# SwitchEthernet_-_Rev_A3.net
KiCad netlist of a schematic drawn in EAGLE
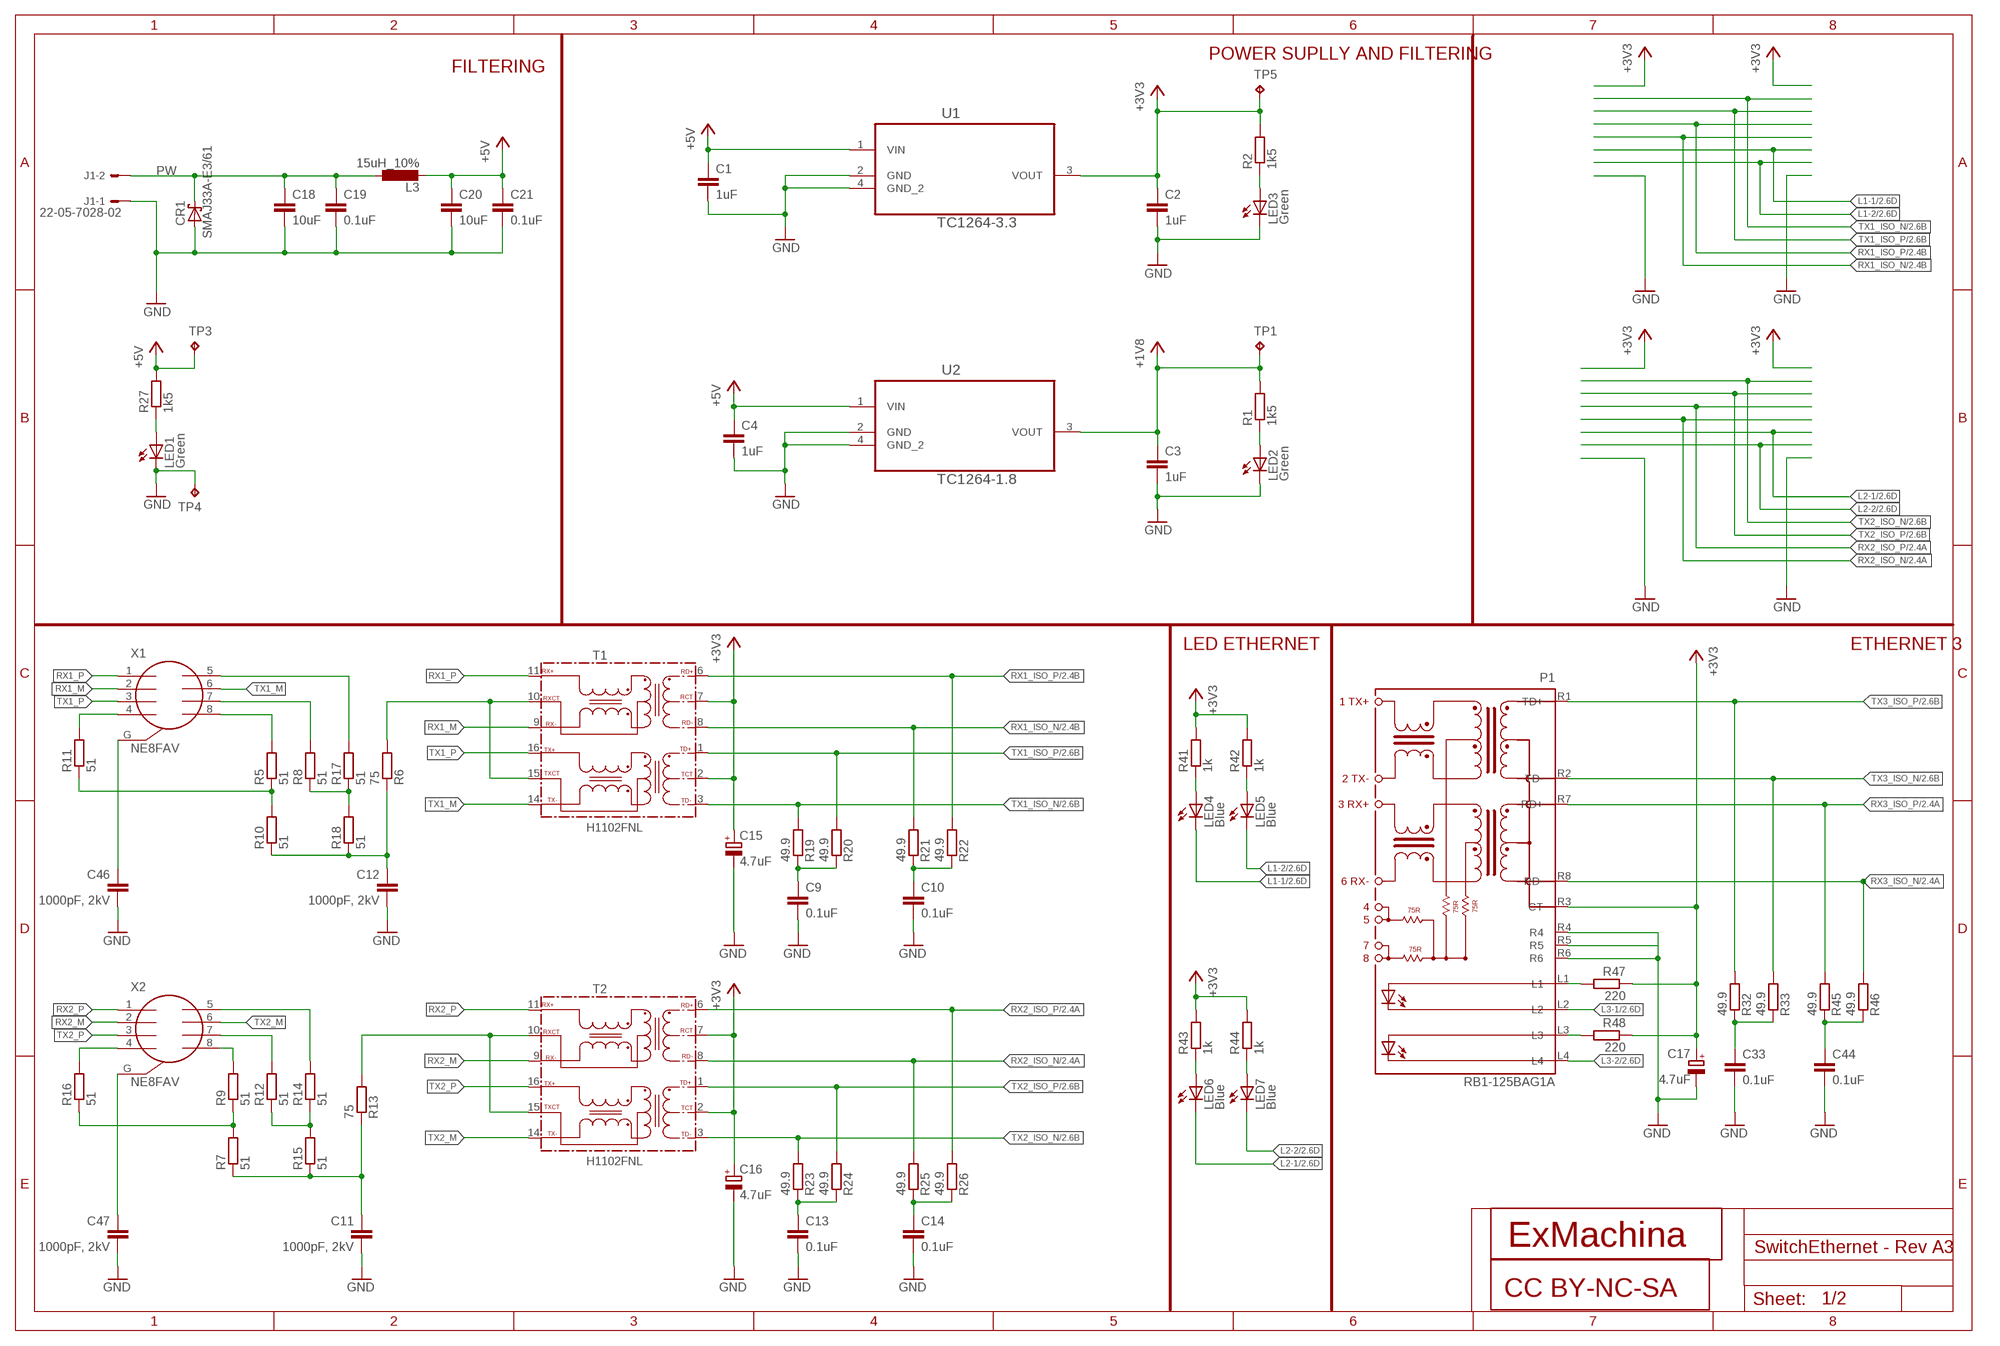
[diagram p0: schematic, sheet 1]
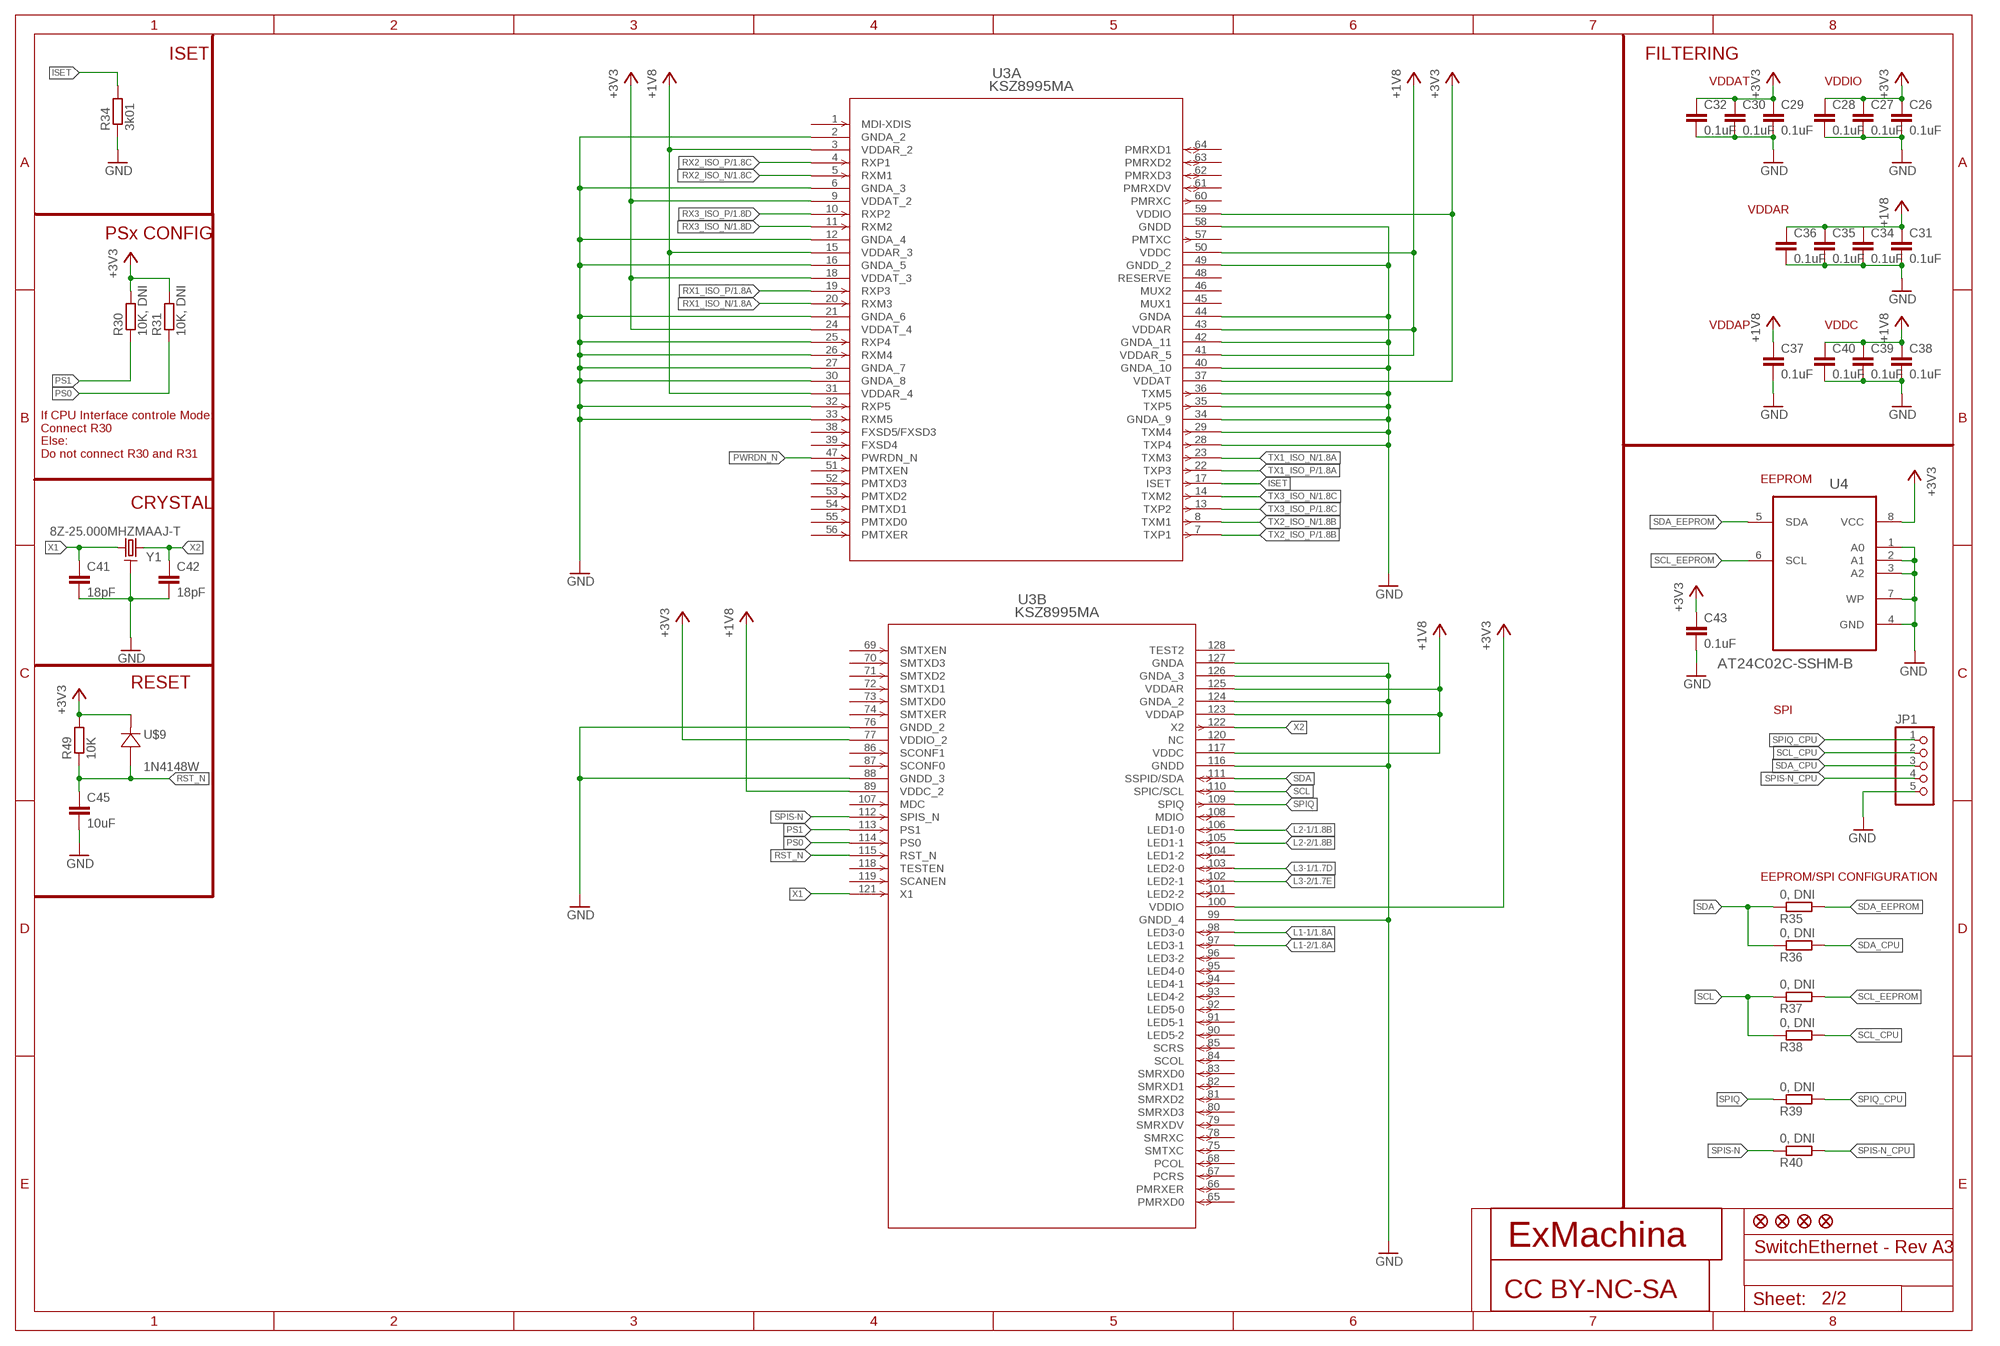
[diagram p1: schematic, sheet 2]

(export (version "E")
  (design (tool "Eeschema 10.0.6"))
  (components
    (comp (ref "C26")
      (value "0.1uF")
      (footprint "eagle-import:C0603")
      (fields (field (name "MF") "MULTICOMP") (field (name "MPN") "MC0603B104K250CT"))
      (libsource (lib "eagle-import") (part "C-EUC0603"))
    )
    (comp (ref "C27")
      (value "0.1uF")
      (footprint "eagle-import:C0603")
      (fields (field (name "MF") "MULTICOMP") (field (name "MPN") "MC0603B104K250CT"))
      (libsource (lib "eagle-import") (part "C-EUC0603"))
    )
    (comp (ref "C28")
      (value "0.1uF")
      (footprint "eagle-import:C0603")
      (fields (field (name "MF") "MULTICOMP") (field (name "MPN") "MC0603B104K250CT"))
      (libsource (lib "eagle-import") (part "C-EUC0603"))
    )
    (comp (ref "C29")
      (value "0.1uF")
      (footprint "eagle-import:C0603")
      (fields (field (name "MF") "MULTICOMP") (field (name "MPN") "MC0603B104K250CT"))
      (libsource (lib "eagle-import") (part "C-EUC0603"))
    )
    (comp (ref "C30")
      (value "0.1uF")
      (footprint "eagle-import:C0603")
      (fields (field (name "MF") "MULTICOMP") (field (name "MPN") "MC0603B104K250CT"))
      (libsource (lib "eagle-import") (part "C-EUC0603"))
    )
    (comp (ref "C31")
      (value "0.1uF")
      (footprint "eagle-import:C0603")
      (fields (field (name "MF") "MULTICOMP") (field (name "MPN") "MC0603B104K250CT"))
      (libsource (lib "eagle-import") (part "C-EUC0603"))
    )
    (comp (ref "C32")
      (value "0.1uF")
      (footprint "eagle-import:C0603")
      (fields (field (name "MF") "MULTICOMP") (field (name "MPN") "MC0603B104K250CT"))
      (libsource (lib "eagle-import") (part "C-EUC0603"))
    )
    (comp (ref "C34")
      (value "0.1uF")
      (footprint "eagle-import:C0603")
      (fields (field (name "MF") "MULTICOMP") (field (name "MPN") "MC0603B104K250CT"))
      (libsource (lib "eagle-import") (part "C-EUC0603"))
    )
    (comp (ref "C35")
      (value "0.1uF")
      (footprint "eagle-import:C0603")
      (fields (field (name "MF") "MULTICOMP") (field (name "MPN") "MC0603B104K250CT"))
      (libsource (lib "eagle-import") (part "C-EUC0603"))
    )
    (comp (ref "C36")
      (value "0.1uF")
      (footprint "eagle-import:C0603")
      (fields (field (name "MF") "MULTICOMP") (field (name "MPN") "MC0603B104K250CT"))
      (libsource (lib "eagle-import") (part "C-EUC0603"))
    )
    (comp (ref "C37")
      (value "0.1uF")
      (footprint "eagle-import:C0603")
      (fields (field (name "MF") "MULTICOMP") (field (name "MPN") "MC0603B104K250CT"))
      (libsource (lib "eagle-import") (part "C-EUC0603"))
    )
    (comp (ref "C38")
      (value "0.1uF")
      (footprint "eagle-import:C0603")
      (fields (field (name "MF") "MULTICOMP") (field (name "MPN") "MC0603B104K250CT"))
      (libsource (lib "eagle-import") (part "C-EUC0603"))
    )
    (comp (ref "C39")
      (value "0.1uF")
      (footprint "eagle-import:C0603")
      (fields (field (name "MF") "MULTICOMP") (field (name "MPN") "MC0603B104K250CT"))
      (libsource (lib "eagle-import") (part "C-EUC0603"))
    )
    (comp (ref "C40")
      (value "0.1uF")
      (footprint "eagle-import:C0603")
      (fields (field (name "MF") "MULTICOMP") (field (name "MPN") "MC0603B104K250CT"))
      (libsource (lib "eagle-import") (part "C-EUC0603"))
    )
    (comp (ref "C41")
      (value "18pF")
      (footprint "eagle-import:C0603")
      (fields (field (name "MF") "MULTICOMP") (field (name "MPN") "MC0603B183K160CT"))
      (libsource (lib "eagle-import") (part "C-EUC0603"))
    )
    (comp (ref "C42")
      (value "18pF")
      (footprint "eagle-import:C0603")
      (fields (field (name "MF") "MULTICOMP") (field (name "MPN") "MC0603B183K160CT"))
      (libsource (lib "eagle-import") (part "C-EUC0603"))
    )
    (comp (ref "C43")
      (value "0.1uF")
      (footprint "eagle-import:C0603")
      (fields (field (name "MF") "MULTICOMP") (field (name "MPN") "MC0603B104K250CT"))
      (libsource (lib "eagle-import") (part "C-EUC0603"))
    )
    (comp (ref "C45")
      (value "10uF")
      (footprint "eagle-import:C0603")
      (fields (field (name "MF") "MURATA") (field (name "MPN") "GRM32DR71C106KA01L"))
      (libsource (lib "eagle-import") (part "C-EUC0603"))
    )
    (comp (ref "JP1")
      (value "PINHD-1X5")
      (footprint "eagle-import:1X05")
      (libsource (lib "eagle-import") (part "PINHD-1X5"))
    )
    (comp (ref "JP7")
      (value "FIDUCIAL1X2")
      (footprint "eagle-import:FIDUCIAL-1X2")
      (libsource (lib "eagle-import") (part "FIDUCIAL1X2"))
    )
    (comp (ref "JP8")
      (value "FIDUCIAL1X2")
      (footprint "eagle-import:FIDUCIAL-1X2")
      (libsource (lib "eagle-import") (part "FIDUCIAL1X2"))
    )
    (comp (ref "JP9")
      (value "FIDUCIAL1X2")
      (footprint "eagle-import:FIDUCIAL-1X2")
      (libsource (lib "eagle-import") (part "FIDUCIAL1X2"))
    )
    (comp (ref "JP10")
      (value "FIDUCIAL1X2")
      (footprint "eagle-import:FIDUCIAL-1X2")
      (libsource (lib "eagle-import") (part "FIDUCIAL1X2"))
    )
    (comp (ref "R30")
      (value "10K, DNI")
      (footprint "eagle-import:R0603")
      (libsource (lib "eagle-import") (part "R-EU_R0603"))
    )
    (comp (ref "R31")
      (value "10K, DNI")
      (footprint "eagle-import:R0603")
      (libsource (lib "eagle-import") (part "R-EU_R0603"))
    )
    (comp (ref "R34")
      (value "3k01")
      (footprint "eagle-import:R0603")
      (fields (field (name "MF") "MULTICOMP") (field (name "MPN") "MCMR06X3001FTL"))
      (libsource (lib "eagle-import") (part "R-EU_R0603"))
    )
    (comp (ref "R35")
      (value "0, DNI")
      (footprint "eagle-import:R0603")
      (libsource (lib "eagle-import") (part "R-EU_R0603"))
    )
    (comp (ref "R36")
      (value "0, DNI")
      (footprint "eagle-import:R0603")
      (libsource (lib "eagle-import") (part "R-EU_R0603"))
    )
    (comp (ref "R37")
      (value "0, DNI")
      (footprint "eagle-import:R0603")
      (libsource (lib "eagle-import") (part "R-EU_R0603"))
    )
    (comp (ref "R38")
      (value "0, DNI")
      (footprint "eagle-import:R0603")
      (libsource (lib "eagle-import") (part "R-EU_R0603"))
    )
    (comp (ref "R39")
      (value "0, DNI")
      (footprint "eagle-import:R0603")
      (libsource (lib "eagle-import") (part "R-EU_R0603"))
    )
    (comp (ref "R40")
      (value "0, DNI")
      (footprint "eagle-import:R0603")
      (libsource (lib "eagle-import") (part "R-EU_R0603"))
    )
    (comp (ref "R49")
      (value "10K")
      (footprint "eagle-import:R0603")
      (fields (field (name "MF") "MULTICOMP") (field (name "MPN") "MCMR06X1002FTL"))
      (libsource (lib "eagle-import") (part "R-EU_R0603"))
    )
    (comp (ref "U$7")
      (value "CC-BY-NC-SA")
      (footprint "eagle-import:CC-BY-NC-SA")
      (libsource (lib "eagle-import") (part "CC-BY-NC-SA"))
    )
    (comp (ref "U$8")
      (value "EXMACHINA-LOGO-NAME")
      (footprint "eagle-import:EXM-LOGO-BASELINE")
      (libsource (lib "eagle-import") (part "EXMACHINA-LOGO-NAME"))
    )
    (comp (ref "U$9")
      (value "1N4148W")
      (footprint "eagle-import:SOD-123_MINI-SMA")
      (libsource (lib "eagle-import") (part "1N4148W"))
    )
    (comp (ref "U3")
      (value "KSZ8995MA")
      (footprint "eagle-import:PQFP-128_MQL")
      (fields
        (field (name "MANUFACTURER_PART_NUMBER") "ksz8995ma")
        (field (name "MF") "MICROCHIP")
        (field (name "MPN") "KSZ8995MA")
        (field (name "OC_FARNELL") "2509844")
        (field (name "OC_NEWARK") "70Y9044")
        (field (name "COPYRIGHT") "Copyright (C) 2015 Accelerated Designs. All rights reserved")
      )
      (libsource (lib "eagle-import") (part "KSZ8995MA"))
    )
    (comp (ref "U4")
      (value "AT24C02C-SSHM-B")
      (footprint "eagle-import:SOIC127P600X175-8N")
      (fields (field (name "MF") "ATMEL") (field (name "OC_FARNELL") "1971995"))
      (libsource (lib "eagle-import") (part "AT24C02C-SSHM-B"))
    )
    (comp (ref "Y1")
      (value "8Z-25.000MHZMAAJ-T")
      (footprint "eagle-import:SMD2.5X2")
      (fields (field (name "MF") "TXC") (field (name "MPN") "8Z-25.000MAAJ-T"))
      (libsource (lib "eagle-import") (part "8Z-25.000MHZMAAJ-T"))
    )
    (comp (ref "C1")
      (value "1uF")
      (footprint "eagle-import:C0603")
      (libsource (lib "eagle-import") (part "C-EUC0603"))
    )
    (comp (ref "C2")
      (value "1uF")
      (footprint "eagle-import:C0603")
      (libsource (lib "eagle-import") (part "C-EUC0603"))
    )
    (comp (ref "C3")
      (value "1uF")
      (footprint "eagle-import:C0603")
      (libsource (lib "eagle-import") (part "C-EUC0603"))
    )
    (comp (ref "C4")
      (value "1uF")
      (footprint "eagle-import:C0603")
      (libsource (lib "eagle-import") (part "C-EUC0603"))
    )
    (comp (ref "C9")
      (value "0.1uF")
      (footprint "eagle-import:C0603")
      (fields (field (name "MF") "MULTICOMP") (field (name "MPN") "MC0603B104K250CT"))
      (libsource (lib "eagle-import") (part "C-EUC0603"))
    )
    (comp (ref "C10")
      (value "0.1uF")
      (footprint "eagle-import:C0603")
      (fields (field (name "MF") "MULTICOMP") (field (name "MPN") "MC0603B104K250CT"))
      (libsource (lib "eagle-import") (part "C-EUC0603"))
    )
    (comp (ref "C11")
      (value "1000pF, 2kV")
      (footprint "eagle-import:C1206")
      (libsource (lib "eagle-import") (part "C-EUC1206"))
    )
    (comp (ref "C12")
      (value "1000pF, 2kV")
      (footprint "eagle-import:C1206")
      (libsource (lib "eagle-import") (part "C-EUC1206"))
    )
    (comp (ref "C13")
      (value "0.1uF")
      (footprint "eagle-import:C0603")
      (fields (field (name "MF") "MULTICOMP") (field (name "MPN") "MC0603B104K250CT"))
      (libsource (lib "eagle-import") (part "C-EUC0603"))
    )
    (comp (ref "C14")
      (value "0.1uF")
      (footprint "eagle-import:C0603")
      (fields (field (name "MF") "MULTICOMP") (field (name "MPN") "MC0603B104K250CT"))
      (libsource (lib "eagle-import") (part "C-EUC0603"))
    )
    (comp (ref "C15")
      (value "4.7uF")
      (footprint "eagle-import:CT3216")
      (libsource (lib "eagle-import") (part "CPOL-EUCT3216"))
    )
    (comp (ref "C16")
      (value "4.7uF")
      (footprint "eagle-import:CT3216")
      (libsource (lib "eagle-import") (part "CPOL-EUCT3216"))
    )
    (comp (ref "C17")
      (value "4.7uF")
      (footprint "eagle-import:CT3216")
      (libsource (lib "eagle-import") (part "CPOL-EUCT3216"))
    )
    (comp (ref "C18")
      (value "10uF")
      (footprint "eagle-import:C0603")
      (fields (field (name "MF") "MURATA") (field (name "MPN") "GRM32DR71C106KA01L"))
      (libsource (lib "eagle-import") (part "C-EUC0603"))
    )
    (comp (ref "C19")
      (value "0.1uF")
      (footprint "eagle-import:C0603")
      (fields (field (name "MF") "MULTICOMP") (field (name "MPN") "MC0603B104K250CT"))
      (libsource (lib "eagle-import") (part "C-EUC0603"))
    )
    (comp (ref "C20")
      (value "10uF")
      (footprint "eagle-import:C0603")
      (fields (field (name "MF") "MURATA") (field (name "MPN") "GRM32DR71C106KA01L"))
      (libsource (lib "eagle-import") (part "C-EUC0603"))
    )
    (comp (ref "C21")
      (value "0.1uF")
      (footprint "eagle-import:C0603")
      (fields (field (name "MF") "MULTICOMP") (field (name "MPN") "MC0603B104K250CT"))
      (libsource (lib "eagle-import") (part "C-EUC0603"))
    )
    (comp (ref "C33")
      (value "0.1uF")
      (footprint "eagle-import:C0603")
      (fields (field (name "MF") "MULTICOMP") (field (name "MPN") "MC0603B104K250CT"))
      (libsource (lib "eagle-import") (part "C-EUC0603"))
    )
    (comp (ref "C44")
      (value "0.1uF")
      (footprint "eagle-import:C0603")
      (fields (field (name "MF") "MULTICOMP") (field (name "MPN") "MC0603B104K250CT"))
      (libsource (lib "eagle-import") (part "C-EUC0603"))
    )
    (comp (ref "C46")
      (value "1000pF, 2kV")
      (footprint "eagle-import:C1206")
      (libsource (lib "eagle-import") (part "C-EUC1206"))
    )
    (comp (ref "C47")
      (value "1000pF, 2kV")
      (footprint "eagle-import:C1206")
      (libsource (lib "eagle-import") (part "C-EUC1206"))
    )
    (comp (ref "CR1")
      (value "SMAJ33A-E3/61")
      (footprint "eagle-import:DIODE_DO-214AC")
      (fields
        (field (name "RSPARTNUMBER") "7103462")
        (field (name "MF") "VISHAY")
        (field (name "MPN") "SMAJ33A-E3/5A")
        (field (name "COPYRIGHT") "Copyright (C) 2015 Accelerated Designs. All rights reserved")
      )
      (libsource (lib "eagle-import") (part "SMAJ33A-E3/61"))
    )
    (comp (ref "J1")
      (value "22-05-7028-02")
      (footprint "eagle-import:7395-02")
      (fields
        (field (name "MF") "MOLEX")
        (field (name "MPN") "22-05-7028")
        (field (name "OC_NEWARK") "25M1728")
      )
      (libsource (lib "eagle-import") (part "22-?-0205-7028"))
    )
    (comp (ref "L3")
      (value "15uH_10%")
      (footprint "eagle-import:L4532M")
      (libsource (lib "eagle-import") (part "L-EUL4532C"))
    )
    (comp (ref "LED1")
      (value "Green")
      (footprint "eagle-import:CHIP-LED0603")
      (fields (field (name "MF") "MULTICOMP") (field (name "MPN") "OVS-0604"))
      (libsource (lib "eagle-import") (part "LEDCHIP-LED0603"))
    )
    (comp (ref "LED2")
      (value "Green")
      (footprint "eagle-import:CHIP-LED0603")
      (fields (field (name "MF") "MULTICOMP") (field (name "MPN") "OVS-0604"))
      (libsource (lib "eagle-import") (part "LEDCHIP-LED0603"))
    )
    (comp (ref "LED3")
      (value "Green")
      (footprint "eagle-import:CHIP-LED0603")
      (fields (field (name "MF") "MULTICOMP") (field (name "MPN") "OVS-0604"))
      (libsource (lib "eagle-import") (part "LEDCHIP-LED0603"))
    )
    (comp (ref "LED4")
      (value "Blue")
      (footprint "eagle-import:CHIP-LED0603")
      (fields (field (name "MF") "MULTICOMP") (field (name "MPN") "OVS-0603"))
      (libsource (lib "eagle-import") (part "LEDCHIP-LED0603"))
    )
    (comp (ref "LED5")
      (value "Blue")
      (footprint "eagle-import:CHIP-LED0603")
      (fields (field (name "MF") "MULTICOMP") (field (name "MPN") "OVS-0603"))
      (libsource (lib "eagle-import") (part "LEDCHIP-LED0603"))
    )
    (comp (ref "LED6")
      (value "Blue")
      (footprint "eagle-import:CHIP-LED0603")
      (fields (field (name "MF") "MULTICOMP") (field (name "MPN") "OVS-0603"))
      (libsource (lib "eagle-import") (part "LEDCHIP-LED0603"))
    )
    (comp (ref "LED7")
      (value "Blue")
      (footprint "eagle-import:CHIP-LED0603")
      (fields (field (name "MF") "MULTICOMP") (field (name "MPN") "OVS-0603"))
      (libsource (lib "eagle-import") (part "LEDCHIP-LED0603"))
    )
    (comp (ref "P1")
      (value "RB1-125BAG1A")
      (footprint "eagle-import:WIZNET_RB1-125BAG1A")
      (libsource (lib "eagle-import") (part "RB1-125BAG1A"))
    )
    (comp (ref "R1")
      (value "1k5")
      (footprint "eagle-import:R0603")
      (fields (field (name "MF") "MULTICOMP") (field (name "MPN") "MCMR06X1501FTL"))
      (libsource (lib "eagle-import") (part "R-EU_R0603"))
    )
    (comp (ref "R2")
      (value "1k5")
      (footprint "eagle-import:R0603")
      (fields (field (name "MF") "MULTICOMP") (field (name "MPN") "MCMR06X1501FTL"))
      (libsource (lib "eagle-import") (part "R-EU_R0603"))
    )
    (comp (ref "R5")
      (value "51")
      (footprint "eagle-import:R0603")
      (fields (field (name "MF") "MULTICOMP") (field (name "MPN") "MCMR06X49R9FTL"))
      (libsource (lib "eagle-import") (part "R-EU_R0603"))
    )
    (comp (ref "R6")
      (value "75")
      (footprint "eagle-import:R0603")
      (fields (field (name "MF") "MULTICOMP") (field (name "MPN") "MCMR06X75R0FTL"))
      (libsource (lib "eagle-import") (part "R-EU_R0603"))
    )
    (comp (ref "R7")
      (value "51")
      (footprint "eagle-import:R0603")
      (fields (field (name "MF") "MULTICOMP") (field (name "MPN") "MCMR06X49R9FTL"))
      (libsource (lib "eagle-import") (part "R-EU_R0603"))
    )
    (comp (ref "R8")
      (value "51")
      (footprint "eagle-import:R0603")
      (fields (field (name "MF") "MULTICOMP") (field (name "MPN") "MCMR06X49R9FTL"))
      (libsource (lib "eagle-import") (part "R-EU_R0603"))
    )
    (comp (ref "R9")
      (value "51")
      (footprint "eagle-import:R0603")
      (fields (field (name "MF") "MULTICOMP") (field (name "MPN") "MCMR06X49R9FTL"))
      (libsource (lib "eagle-import") (part "R-EU_R0603"))
    )
    (comp (ref "R10")
      (value "51")
      (footprint "eagle-import:R0603")
      (fields (field (name "MF") "MULTICOMP") (field (name "MPN") "MCMR06X49R9FTL"))
      (libsource (lib "eagle-import") (part "R-EU_R0603"))
    )
    (comp (ref "R11")
      (value "51")
      (footprint "eagle-import:R0603")
      (fields (field (name "MF") "MULTICOMP") (field (name "MPN") "MCMR06X49R9FTL"))
      (libsource (lib "eagle-import") (part "R-EU_R0603"))
    )
    (comp (ref "R12")
      (value "51")
      (footprint "eagle-import:R0603")
      (fields (field (name "MF") "MULTICOMP") (field (name "MPN") "MCMR06X49R9FTL"))
      (libsource (lib "eagle-import") (part "R-EU_R0603"))
    )
    (comp (ref "R13")
      (value "75")
      (footprint "eagle-import:R0603")
      (fields (field (name "MF") "MULTICOMP") (field (name "MPN") "MCMR06X75R0FTL"))
      (libsource (lib "eagle-import") (part "R-EU_R0603"))
    )
    (comp (ref "R14")
      (value "51")
      (footprint "eagle-import:R0603")
      (fields (field (name "MF") "MULTICOMP") (field (name "MPN") "MCMR06X49R9FTL"))
      (libsource (lib "eagle-import") (part "R-EU_R0603"))
    )
    (comp (ref "R15")
      (value "51")
      (footprint "eagle-import:R0603")
      (fields (field (name "MF") "MULTICOMP") (field (name "MPN") "MCMR06X49R9FTL"))
      (libsource (lib "eagle-import") (part "R-EU_R0603"))
    )
    (comp (ref "R16")
      (value "51")
      (footprint "eagle-import:R0603")
      (fields (field (name "MF") "MULTICOMP") (field (name "MPN") "MCMR06X49R9FTL"))
      (libsource (lib "eagle-import") (part "R-EU_R0603"))
    )
    (comp (ref "R17")
      (value "51")
      (footprint "eagle-import:R0603")
      (fields (field (name "MF") "MULTICOMP") (field (name "MPN") "MCMR06X49R9FTL"))
      (libsource (lib "eagle-import") (part "R-EU_R0603"))
    )
    (comp (ref "R18")
      (value "51")
      (footprint "eagle-import:R0603")
      (fields (field (name "MF") "MULTICOMP") (field (name "MPN") "MCMR06X49R9FTL"))
      (libsource (lib "eagle-import") (part "R-EU_R0603"))
    )
    (comp (ref "R19")
      (value "49.9")
      (footprint "eagle-import:R0603")
      (fields (field (name "MF") "MULTICOMP") (field (name "MPN") "MCMR06X49R9FTL"))
      (libsource (lib "eagle-import") (part "R-EU_R0603"))
    )
    (comp (ref "R20")
      (value "49.9")
      (footprint "eagle-import:R0603")
      (fields (field (name "MF") "MULTICOMP") (field (name "MPN") "MCMR06X49R9FTL"))
      (libsource (lib "eagle-import") (part "R-EU_R0603"))
    )
    (comp (ref "R21")
      (value "49.9")
      (footprint "eagle-import:R0603")
      (fields (field (name "MF") "MULTICOMP") (field (name "MPN") "MCMR06X49R9FTL"))
      (libsource (lib "eagle-import") (part "R-EU_R0603"))
    )
    (comp (ref "R22")
      (value "49.9")
      (footprint "eagle-import:R0603")
      (fields (field (name "MF") "MULTICOMP") (field (name "MPN") "MCMR06X49R9FTL"))
      (libsource (lib "eagle-import") (part "R-EU_R0603"))
    )
    (comp (ref "R23")
      (value "49.9")
      (footprint "eagle-import:R0603")
      (fields (field (name "MF") "MULTICOMP") (field (name "MPN") "MCMR06X49R9FTL"))
      (libsource (lib "eagle-import") (part "R-EU_R0603"))
    )
    (comp (ref "R24")
      (value "49.9")
      (footprint "eagle-import:R0603")
      (fields (field (name "MF") "MULTICOMP") (field (name "MPN") "MCMR06X49R9FTL"))
      (libsource (lib "eagle-import") (part "R-EU_R0603"))
    )
    (comp (ref "R25")
      (value "49.9")
      (footprint "eagle-import:R0603")
      (fields (field (name "MF") "MULTICOMP") (field (name "MPN") "MCMR06X49R9FTL"))
      (libsource (lib "eagle-import") (part "R-EU_R0603"))
    )
    (comp (ref "R26")
      (value "49.9")
      (footprint "eagle-import:R0603")
      (fields (field (name "MF") "MULTICOMP") (field (name "MPN") "MCMR06X49R9FTL"))
      (libsource (lib "eagle-import") (part "R-EU_R0603"))
    )
    (comp (ref "R27")
      (value "1k5")
      (footprint "eagle-import:R0603")
      (fields (field (name "MF") "MULTICOMP") (field (name "MPN") "MCMR06X1501FTL"))
      (libsource (lib "eagle-import") (part "R-EU_R0603"))
    )
    (comp (ref "R32")
      (value "49.9")
      (footprint "eagle-import:R0603")
      (fields (field (name "MF") "MULTICOMP") (field (name "MPN") "MCMR06X49R9FTL"))
      (libsource (lib "eagle-import") (part "R-EU_R0603"))
    )
    (comp (ref "R33")
      (value "49.9")
      (footprint "eagle-import:R0603")
      (fields (field (name "MF") "MULTICOMP") (field (name "MPN") "MCMR06X49R9FTL"))
      (libsource (lib "eagle-import") (part "R-EU_R0603"))
    )
    (comp (ref "R41")
      (value "1k")
      (footprint "eagle-import:R0603")
      (fields (field (name "MF") "MULTICOMP") (field (name "MPN") "MCMR06X1001FTL"))
      (libsource (lib "eagle-import") (part "R-EU_R0603"))
    )
    (comp (ref "R42")
      (value "1k")
      (footprint "eagle-import:R0603")
      (fields (field (name "MF") "MULTICOMP") (field (name "MPN") "MCMR06X1001FTL"))
      (libsource (lib "eagle-import") (part "R-EU_R0603"))
    )
    (comp (ref "R43")
      (value "1k")
      (footprint "eagle-import:R0603")
      (fields (field (name "MF") "MULTICOMP") (field (name "MPN") "MCMR06X1001FTL"))
      (libsource (lib "eagle-import") (part "R-EU_R0603"))
    )
    (comp (ref "R44")
      (value "1k")
      (footprint "eagle-import:R0603")
      (fields (field (name "MF") "MULTICOMP") (field (name "MPN") "MCMR06X1001FTL"))
      (libsource (lib "eagle-import") (part "R-EU_R0603"))
    )
    (comp (ref "R45")
      (value "49.9")
      (footprint "eagle-import:R0603")
      (fields (field (name "MF") "MULTICOMP") (field (name "MPN") "MCMR06X49R9FTL"))
      (libsource (lib "eagle-import") (part "R-EU_R0603"))
    )
    (comp (ref "R46")
      (value "49.9")
      (footprint "eagle-import:R0603")
      (fields (field (name "MF") "MULTICOMP") (field (name "MPN") "MCMR06X49R9FTL"))
      (libsource (lib "eagle-import") (part "R-EU_R0603"))
    )
    (comp (ref "R47")
      (value "220")
      (footprint "eagle-import:R0603")
      (fields (field (name "MF") "MULTICOMP") (field (name "MPN") "MCMR06X2200FTL"))
      (libsource (lib "eagle-import") (part "R-EU_R0603"))
    )
    (comp (ref "R48")
      (value "220")
      (footprint "eagle-import:R0603")
      (fields (field (name "MF") "MULTICOMP") (field (name "MPN") "MCMR06X2200FTL"))
      (libsource (lib "eagle-import") (part "R-EU_R0603"))
    )
    (comp (ref "T1")
      (value "H1102FNL")
      (footprint "eagle-import:HXXXX")
      (libsource (lib "eagle-import") (part "H1102FNL"))
    )
    (comp (ref "T2")
      (value "H1102FNL")
      (footprint "eagle-import:HXXXX")
      (libsource (lib "eagle-import") (part "H1102FNL"))
    )
    (comp (ref "TP1")
      (value "TPB1,27")
      (footprint "eagle-import:B1,27")
      (libsource (lib "eagle-import") (part "TPB1,27"))
    )
    (comp (ref "TP3")
      (value "TPB1,27")
      (footprint "eagle-import:B1,27")
      (libsource (lib "eagle-import") (part "TPB1,27"))
    )
    (comp (ref "TP4")
      (value "TPB1,27")
      (footprint "eagle-import:B1,27")
      (libsource (lib "eagle-import") (part "TPB1,27"))
    )
    (comp (ref "TP5")
      (value "TPB1,27")
      (footprint "eagle-import:B1,27")
      (libsource (lib "eagle-import") (part "TPB1,27"))
    )
    (comp (ref "U$5")
      (value "EXMACHINA-LOGO-NAME")
      (footprint "eagle-import:EXM-LOGO-BASELINE")
      (libsource (lib "eagle-import") (part "EXMACHINA-LOGO-NAME"))
    )
    (comp (ref "U$6")
      (value "CC-BY-NC-SA")
      (footprint "eagle-import:CC-BY-NC-SA")
      (libsource (lib "eagle-import") (part "CC-BY-NC-SA"))
    )
    (comp (ref "U1")
      (value "TC1264-3.3")
      (footprint "eagle-import:SOT230P700X180-4N")
      (libsource (lib "eagle-import") (part "TC1264-3.3"))
    )
    (comp (ref "U2")
      (value "TC1264-1.8")
      (footprint "eagle-import:SOT230P700X180-4N")
      (libsource (lib "eagle-import") (part "TC1264-1.8"))
    )
    (comp (ref "X1")
      (value "NE8FAV")
      (footprint "eagle-import:NE8FAV")
      (fields (field (name "MF") "NEUTRIK") (field (name "OC_FARNELL") "1202031"))
      (libsource (lib "eagle-import") (part "NE8FAV"))
    )
    (comp (ref "X2")
      (value "NE8FAV")
      (footprint "eagle-import:NE8FAV")
      (fields (field (name "MF") "NEUTRIK") (field (name "OC_FARNELL") "1202031"))
      (libsource (lib "eagle-import") (part "NE8FAV"))
    )
  )
  (nets
    (net (code "1") (name "+1V8") (class "Default")
      (node (ref "C3") (pin "1") (pinfunction "1_1") (pintype "passive"))
      (node (ref "C31") (pin "1") (pinfunction "1_1") (pintype "passive"))
      (node (ref "C34") (pin "1") (pinfunction "1_1") (pintype "passive"))
      (node (ref "C35") (pin "1") (pinfunction "1_1") (pintype "passive"))
      (node (ref "C36") (pin "1") (pinfunction "1_1") (pintype "passive"))
      (node (ref "C37") (pin "1") (pinfunction "1_1") (pintype "passive"))
      (node (ref "C38") (pin "1") (pinfunction "1_1") (pintype "passive"))
      (node (ref "C39") (pin "1") (pinfunction "1_1") (pintype "passive"))
      (node (ref "C40") (pin "1") (pinfunction "1_1") (pintype "passive"))
      (node (ref "R1") (pin "2") (pinfunction "2_2") (pintype "passive"))
      (node (ref "TP1") (pin "TP") (pinfunction "TP_TP") (pintype "input"))
      (node (ref "U2") (pin "3") (pinfunction "VOUT_3") (pintype "output"))
      (node (ref "U3") (pin "117") (pinfunction "VDDC_117") (pintype "power_in"))
      (node (ref "U3") (pin "123") (pinfunction "VDDAP_123") (pintype "power_in"))
      (node (ref "U3") (pin "125") (pinfunction "VDDAR_125") (pintype "power_in"))
      (node (ref "U3") (pin "15") (pinfunction "VDDAR_3_15") (pintype "power_in"))
      (node (ref "U3") (pin "3") (pinfunction "VDDAR_2_3") (pintype "power_in"))
      (node (ref "U3") (pin "31") (pinfunction "VDDAR_4_31") (pintype "power_in"))
      (node (ref "U3") (pin "41") (pinfunction "VDDAR_5_41") (pintype "power_in"))
      (node (ref "U3") (pin "43") (pinfunction "VDDAR_43") (pintype "power_in"))
      (node (ref "U3") (pin "50") (pinfunction "VDDC_50") (pintype "power_in"))
      (node (ref "U3") (pin "89") (pinfunction "VDDC_2_89") (pintype "power_in"))
    )
    (net (code "2") (name "+3V3") (class "Default")
      (node (ref "C15") (pin "+") (pinfunction "+_+") (pintype "passive"))
      (node (ref "C16") (pin "+") (pinfunction "+_+") (pintype "passive"))
      (node (ref "C17") (pin "+") (pinfunction "+_+") (pintype "passive"))
      (node (ref "C2") (pin "1") (pinfunction "1_1") (pintype "passive"))
      (node (ref "C26") (pin "1") (pinfunction "1_1") (pintype "passive"))
      (node (ref "C27") (pin "1") (pinfunction "1_1") (pintype "passive"))
      (node (ref "C28") (pin "1") (pinfunction "1_1") (pintype "passive"))
      (node (ref "C29") (pin "1") (pinfunction "1_1") (pintype "passive"))
      (node (ref "C30") (pin "1") (pinfunction "1_1") (pintype "passive"))
      (node (ref "C32") (pin "1") (pinfunction "1_1") (pintype "passive"))
      (node (ref "C43") (pin "1") (pinfunction "1_1") (pintype "passive"))
      (node (ref "P1") (pin "R3") (pinfunction "CT_R3") (pintype "input"))
      (node (ref "R2") (pin "2") (pinfunction "2_2") (pintype "passive"))
      (node (ref "R30") (pin "2") (pinfunction "2_2") (pintype "passive"))
      (node (ref "R31") (pin "2") (pinfunction "2_2") (pintype "passive"))
      (node (ref "R41") (pin "2") (pinfunction "2_2") (pintype "passive"))
      (node (ref "R42") (pin "2") (pinfunction "2_2") (pintype "passive"))
      (node (ref "R43") (pin "2") (pinfunction "2_2") (pintype "passive"))
      (node (ref "R44") (pin "2") (pinfunction "2_2") (pintype "passive"))
      (node (ref "R47") (pin "1") (pinfunction "1_1") (pintype "passive"))
      (node (ref "R48") (pin "1") (pinfunction "1_1") (pintype "passive"))
      (node (ref "R49") (pin "2") (pinfunction "2_2") (pintype "passive"))
      (node (ref "T1") (pin "2") (pinfunction "TCT_2") (pintype "bidirectional"))
      (node (ref "T1") (pin "7") (pinfunction "RCT_7") (pintype "bidirectional"))
      (node (ref "T2") (pin "2") (pinfunction "TCT_2") (pintype "bidirectional"))
      (node (ref "T2") (pin "7") (pinfunction "RCT_7") (pintype "bidirectional"))
      (node (ref "TP5") (pin "TP") (pinfunction "TP_TP") (pintype "input"))
      (node (ref "U$9") (pin "C") (pinfunction "1_C") (pintype "passive"))
      (node (ref "U1") (pin "3") (pinfunction "VOUT_3") (pintype "output"))
      (node (ref "U3") (pin "100") (pinfunction "VDDIO_100") (pintype "power_in"))
      (node (ref "U3") (pin "18") (pinfunction "VDDAT_3_18") (pintype "power_in"))
      (node (ref "U3") (pin "24") (pinfunction "VDDAT_4_24") (pintype "power_in"))
      (node (ref "U3") (pin "37") (pinfunction "VDDAT_37") (pintype "power_in"))
      (node (ref "U3") (pin "59") (pinfunction "VDDIO_59") (pintype "power_in"))
      (node (ref "U3") (pin "77") (pinfunction "VDDIO_2_77") (pintype "power_in"))
      (node (ref "U3") (pin "9") (pinfunction "VDDAT_2_9") (pintype "power_in"))
      (node (ref "U4") (pin "8") (pinfunction "VCC_8") (pintype "power_in"))
    )
    (net (code "3") (name "+5V") (class "Default")
      (node (ref "C1") (pin "1") (pinfunction "1_1") (pintype "passive"))
      (node (ref "C20") (pin "1") (pinfunction "1_1") (pintype "passive"))
      (node (ref "C21") (pin "1") (pinfunction "1_1") (pintype "passive"))
      (node (ref "C4") (pin "1") (pinfunction "1_1") (pintype "passive"))
      (node (ref "L3") (pin "2") (pinfunction "2_2") (pintype "passive"))
      (node (ref "R27") (pin "2") (pinfunction "2_2") (pintype "passive"))
      (node (ref "TP3") (pin "TP") (pinfunction "TP_TP") (pintype "input"))
      (node (ref "U1") (pin "1") (pinfunction "VIN_1") (pintype "input"))
      (node (ref "U2") (pin "1") (pinfunction "VIN_1") (pintype "input"))
    )
    (net (code "4") (name "GND") (class "Default")
      (node (ref "C1") (pin "2") (pinfunction "2_2") (pintype "passive"))
      (node (ref "C10") (pin "2") (pinfunction "2_2") (pintype "passive"))
      (node (ref "C11") (pin "2") (pinfunction "2_2") (pintype "passive"))
      (node (ref "C12") (pin "2") (pinfunction "2_2") (pintype "passive"))
      (node (ref "C13") (pin "2") (pinfunction "2_2") (pintype "passive"))
      (node (ref "C14") (pin "2") (pinfunction "2_2") (pintype "passive"))
      (node (ref "C15") (pin "-") (pinfunction "-_-") (pintype "passive"))
      (node (ref "C16") (pin "-") (pinfunction "-_-") (pintype "passive"))
      (node (ref "C17") (pin "-") (pinfunction "-_-") (pintype "passive"))
      (node (ref "C18") (pin "2") (pinfunction "2_2") (pintype "passive"))
      (node (ref "C19") (pin "2") (pinfunction "2_2") (pintype "passive"))
      (node (ref "C2") (pin "2") (pinfunction "2_2") (pintype "passive"))
      (node (ref "C20") (pin "2") (pinfunction "2_2") (pintype "passive"))
      (node (ref "C21") (pin "2") (pinfunction "2_2") (pintype "passive"))
      (node (ref "C26") (pin "2") (pinfunction "2_2") (pintype "passive"))
      (node (ref "C27") (pin "2") (pinfunction "2_2") (pintype "passive"))
      (node (ref "C28") (pin "2") (pinfunction "2_2") (pintype "passive"))
      (node (ref "C29") (pin "2") (pinfunction "2_2") (pintype "passive"))
      (node (ref "C3") (pin "2") (pinfunction "2_2") (pintype "passive"))
      (node (ref "C30") (pin "2") (pinfunction "2_2") (pintype "passive"))
      (node (ref "C31") (pin "2") (pinfunction "2_2") (pintype "passive"))
      (node (ref "C32") (pin "2") (pinfunction "2_2") (pintype "passive"))
      (node (ref "C33") (pin "2") (pinfunction "2_2") (pintype "passive"))
      (node (ref "C34") (pin "2") (pinfunction "2_2") (pintype "passive"))
      (node (ref "C35") (pin "2") (pinfunction "2_2") (pintype "passive"))
      (node (ref "C36") (pin "2") (pinfunction "2_2") (pintype "passive"))
      (node (ref "C37") (pin "2") (pinfunction "2_2") (pintype "passive"))
      (node (ref "C38") (pin "2") (pinfunction "2_2") (pintype "passive"))
      (node (ref "C39") (pin "2") (pinfunction "2_2") (pintype "passive"))
      (node (ref "C4") (pin "2") (pinfunction "2_2") (pintype "passive"))
      (node (ref "C40") (pin "2") (pinfunction "2_2") (pintype "passive"))
      (node (ref "C41") (pin "2") (pinfunction "2_2") (pintype "passive"))
      (node (ref "C42") (pin "2") (pinfunction "2_2") (pintype "passive"))
      (node (ref "C43") (pin "2") (pinfunction "2_2") (pintype "passive"))
      (node (ref "C44") (pin "2") (pinfunction "2_2") (pintype "passive"))
      (node (ref "C45") (pin "2") (pinfunction "2_2") (pintype "passive"))
      (node (ref "C46") (pin "2") (pinfunction "2_2") (pintype "passive"))
      (node (ref "C47") (pin "2") (pinfunction "2_2") (pintype "passive"))
      (node (ref "C9") (pin "2") (pinfunction "2_2") (pintype "passive"))
      (node (ref "CR1") (pin "2") (pinfunction "A_2") (pintype "passive"))
      (node (ref "J1") (pin "1") (pinfunction "S_1") (pintype "passive"))
      (node (ref "JP1") (pin "5") (pinfunction "5_5") (pintype "passive"))
      (node (ref "LED1") (pin "C") (pinfunction "C_C") (pintype "passive"))
      (node (ref "LED2") (pin "C") (pinfunction "C_C") (pintype "passive"))
      (node (ref "LED3") (pin "C") (pinfunction "C_C") (pintype "passive"))
      (node (ref "P1") (pin "R4") (pinfunction "R4_R4") (pintype "input"))
      (node (ref "P1") (pin "R5") (pinfunction "R5_R5") (pintype "input"))
      (node (ref "P1") (pin "R6") (pinfunction "R6_R6") (pintype "input"))
      (node (ref "R34") (pin "1") (pinfunction "1_1") (pintype "passive"))
      (node (ref "TP4") (pin "TP") (pinfunction "TP_TP") (pintype "input"))
      (node (ref "U1") (pin "2") (pinfunction "GND_2") (pintype "passive"))
      (node (ref "U1") (pin "4") (pinfunction "GND_2_4") (pintype "passive"))
      (node (ref "U2") (pin "2") (pinfunction "GND_2") (pintype "passive"))
      (node (ref "U2") (pin "4") (pinfunction "GND_2_4") (pintype "passive"))
      (node (ref "U3") (pin "116") (pinfunction "GNDD_116") (pintype "power_in"))
      (node (ref "U3") (pin "12") (pinfunction "GNDA_4_12") (pintype "power_in"))
      (node (ref "U3") (pin "124") (pinfunction "GNDA_2_124") (pintype "power_in"))
      (node (ref "U3") (pin "126") (pinfunction "GNDA_3_126") (pintype "power_in"))
      (node (ref "U3") (pin "127") (pinfunction "GNDA_127") (pintype "power_in"))
      (node (ref "U3") (pin "16") (pinfunction "GNDA_5_16") (pintype "power_in"))
      (node (ref "U3") (pin "2") (pinfunction "GNDA_2_2") (pintype "power_in"))
      (node (ref "U3") (pin "21") (pinfunction "GNDA_6_21") (pintype "power_in"))
      (node (ref "U3") (pin "25") (pinfunction "RXP4_25") (pintype "input"))
      (node (ref "U3") (pin "26") (pinfunction "RXM4_26") (pintype "input"))
      (node (ref "U3") (pin "27") (pinfunction "GNDA_7_27") (pintype "power_in"))
      (node (ref "U3") (pin "28") (pinfunction "TXP4_28") (pintype "output"))
      (node (ref "U3") (pin "29") (pinfunction "TXM4_29") (pintype "output"))
      (node (ref "U3") (pin "30") (pinfunction "GNDA_8_30") (pintype "power_in"))
      (node (ref "U3") (pin "32") (pinfunction "RXP5_32") (pintype "input"))
      (node (ref "U3") (pin "33") (pinfunction "RXM5_33") (pintype "input"))
      (node (ref "U3") (pin "34") (pinfunction "GNDA_9_34") (pintype "power_in"))
      (node (ref "U3") (pin "35") (pinfunction "TXP5_35") (pintype "output"))
      (node (ref "U3") (pin "36") (pinfunction "TXM5_36") (pintype "output"))
      (node (ref "U3") (pin "40") (pinfunction "GNDA_10_40") (pintype "power_in"))
      (node (ref "U3") (pin "42") (pinfunction "GNDA_11_42") (pintype "power_in"))
      (node (ref "U3") (pin "44") (pinfunction "GNDA_44") (pintype "power_in"))
      (node (ref "U3") (pin "49") (pinfunction "GNDD_2_49") (pintype "passive"))
      (node (ref "U3") (pin "58") (pinfunction "GNDD_58") (pintype "power_in"))
      (node (ref "U3") (pin "6") (pinfunction "GNDA_3_6") (pintype "power_in"))
      (node (ref "U3") (pin "76") (pinfunction "GNDD_2_76") (pintype "power_in"))
      (node (ref "U3") (pin "88") (pinfunction "GNDD_3_88") (pintype "power_in"))
      (node (ref "U3") (pin "99") (pinfunction "GNDD_4_99") (pintype "power_in"))
      (node (ref "U4") (pin "1") (pinfunction "A0_1") (pintype "input"))
      (node (ref "U4") (pin "2") (pinfunction "A1_2") (pintype "input"))
      (node (ref "U4") (pin "3") (pinfunction "A2_3") (pintype "input"))
      (node (ref "U4") (pin "4") (pinfunction "GND_4") (pintype "power_in"))
      (node (ref "U4") (pin "7") (pinfunction "WP_7") (pintype "input"))
      (node (ref "Y1") (pin "2") (pinfunction "2_2") (pintype "passive"))
      (node (ref "Y1") (pin "4") (pinfunction "2_4") (pintype "passive"))
    )
    (net (code "5") (name "ISET") (class "Default")
      (node (ref "R34") (pin "2") (pinfunction "2_2") (pintype "passive"))
      (node (ref "U3") (pin "17") (pinfunction "ISET_17") (pintype "output"))
    )
    (net (code "6") (name "L1-1") (class "Default")
      (node (ref "LED4") (pin "C") (pinfunction "C_C") (pintype "passive"))
      (node (ref "U3") (pin "98") (pinfunction "LED3-0_98") (pintype "bidirectional"))
    )
    (net (code "7") (name "L1-2") (class "Default")
      (node (ref "LED5") (pin "C") (pinfunction "C_C") (pintype "passive"))
      (node (ref "U3") (pin "97") (pinfunction "LED3-1_97") (pintype "bidirectional"))
    )
    (net (code "8") (name "L2-1") (class "Default")
      (node (ref "LED6") (pin "C") (pinfunction "C_C") (pintype "passive"))
      (node (ref "U3") (pin "106") (pinfunction "LED1-0_106") (pintype "bidirectional"))
    )
    (net (code "9") (name "L2-2") (class "Default")
      (node (ref "LED7") (pin "C") (pinfunction "C_C") (pintype "passive"))
      (node (ref "U3") (pin "105") (pinfunction "LED1-1_105") (pintype "bidirectional"))
    )
    (net (code "10") (name "L3-1") (class "Default")
      (node (ref "P1") (pin "L2") (pinfunction "L2_L2") (pintype "passive"))
      (node (ref "U3") (pin "103") (pinfunction "LED2-0_103") (pintype "bidirectional"))
    )
    (net (code "11") (name "L3-2") (class "Default")
      (node (ref "P1") (pin "L4") (pinfunction "L4_L4") (pintype "passive"))
      (node (ref "U3") (pin "102") (pinfunction "LED2-1_102") (pintype "bidirectional"))
    )
    (net (code "12") (name "Net-(C9-Pad1)") (class "Default")
      (node (ref "C9") (pin "1") (pinfunction "1_1") (pintype "passive"))
      (node (ref "R19") (pin "1") (pinfunction "1_1") (pintype "passive"))
      (node (ref "R20") (pin "1") (pinfunction "1_1") (pintype "passive"))
    )
    (net (code "13") (name "Net-(C10-Pad1)") (class "Default")
      (node (ref "C10") (pin "1") (pinfunction "1_1") (pintype "passive"))
      (node (ref "R21") (pin "1") (pinfunction "1_1") (pintype "passive"))
      (node (ref "R22") (pin "1") (pinfunction "1_1") (pintype "passive"))
    )
    (net (code "14") (name "Net-(C11-Pad1)") (class "Default")
      (node (ref "C11") (pin "1") (pinfunction "1_1") (pintype "passive"))
      (node (ref "R13") (pin "1") (pinfunction "1_1") (pintype "passive"))
      (node (ref "R15") (pin "1") (pinfunction "1_1") (pintype "passive"))
      (node (ref "R7") (pin "1") (pinfunction "1_1") (pintype "passive"))
    )
    (net (code "15") (name "Net-(C12-Pad1)") (class "Default")
      (node (ref "C12") (pin "1") (pinfunction "1_1") (pintype "passive"))
      (node (ref "R10") (pin "1") (pinfunction "1_1") (pintype "passive"))
      (node (ref "R18") (pin "1") (pinfunction "1_1") (pintype "passive"))
      (node (ref "R6") (pin "1") (pinfunction "1_1") (pintype "passive"))
    )
    (net (code "16") (name "Net-(C13-Pad1)") (class "Default")
      (node (ref "C13") (pin "1") (pinfunction "1_1") (pintype "passive"))
      (node (ref "R23") (pin "1") (pinfunction "1_1") (pintype "passive"))
      (node (ref "R24") (pin "1") (pinfunction "1_1") (pintype "passive"))
    )
    (net (code "17") (name "Net-(C14-Pad1)") (class "Default")
      (node (ref "C14") (pin "1") (pinfunction "1_1") (pintype "passive"))
      (node (ref "R25") (pin "1") (pinfunction "1_1") (pintype "passive"))
      (node (ref "R26") (pin "1") (pinfunction "1_1") (pintype "passive"))
    )
    (net (code "18") (name "Net-(C33-Pad1)") (class "Default")
      (node (ref "C33") (pin "1") (pinfunction "1_1") (pintype "passive"))
      (node (ref "R32") (pin "1") (pinfunction "1_1") (pintype "passive"))
      (node (ref "R33") (pin "1") (pinfunction "1_1") (pintype "passive"))
    )
    (net (code "19") (name "Net-(C44-Pad1)") (class "Default")
      (node (ref "C44") (pin "1") (pinfunction "1_1") (pintype "passive"))
      (node (ref "R45") (pin "1") (pinfunction "1_1") (pintype "passive"))
      (node (ref "R46") (pin "1") (pinfunction "1_1") (pintype "passive"))
    )
    (net (code "20") (name "Net-(C46-Pad1)") (class "Default")
      (node (ref "C46") (pin "1") (pinfunction "1_1") (pintype "passive"))
      (node (ref "X1") (pin "G") (pinfunction "G_G") (pintype "passive"))
    )
    (net (code "21") (name "Net-(C47-Pad1)") (class "Default")
      (node (ref "C47") (pin "1") (pinfunction "1_1") (pintype "passive"))
      (node (ref "X2") (pin "G") (pinfunction "G_G") (pintype "passive"))
    )
    (net (code "22") (name "Net-(LED1-PadA)") (class "Default")
      (node (ref "LED1") (pin "A") (pinfunction "A_A") (pintype "passive"))
      (node (ref "R27") (pin "1") (pinfunction "1_1") (pintype "passive"))
    )
    (net (code "23") (name "Net-(LED2-PadA)") (class "Default")
      (node (ref "LED2") (pin "A") (pinfunction "A_A") (pintype "passive"))
      (node (ref "R1") (pin "1") (pinfunction "1_1") (pintype "passive"))
    )
    (net (code "24") (name "Net-(LED3-PadA)") (class "Default")
      (node (ref "LED3") (pin "A") (pinfunction "A_A") (pintype "passive"))
      (node (ref "R2") (pin "1") (pinfunction "1_1") (pintype "passive"))
    )
    (net (code "25") (name "Net-(LED4-PadA)") (class "Default")
      (node (ref "LED4") (pin "A") (pinfunction "A_A") (pintype "passive"))
      (node (ref "R41") (pin "1") (pinfunction "1_1") (pintype "passive"))
    )
    (net (code "26") (name "Net-(LED5-PadA)") (class "Default")
      (node (ref "LED5") (pin "A") (pinfunction "A_A") (pintype "passive"))
      (node (ref "R42") (pin "1") (pinfunction "1_1") (pintype "passive"))
    )
    (net (code "27") (name "Net-(LED6-PadA)") (class "Default")
      (node (ref "LED6") (pin "A") (pinfunction "A_A") (pintype "passive"))
      (node (ref "R43") (pin "1") (pinfunction "1_1") (pintype "passive"))
    )
    (net (code "28") (name "Net-(LED7-PadA)") (class "Default")
      (node (ref "LED7") (pin "A") (pinfunction "A_A") (pintype "passive"))
      (node (ref "R44") (pin "1") (pinfunction "1_1") (pintype "passive"))
    )
    (net (code "29") (name "Net-(P1-PadL1)") (class "Default")
      (node (ref "P1") (pin "L1") (pinfunction "L1_L1") (pintype "passive"))
      (node (ref "R47") (pin "2") (pinfunction "2_2") (pintype "passive"))
    )
    (net (code "30") (name "Net-(P1-PadL3)") (class "Default")
      (node (ref "P1") (pin "L3") (pinfunction "L3_L3") (pintype "passive"))
      (node (ref "R48") (pin "2") (pinfunction "2_2") (pintype "passive"))
    )
    (net (code "31") (name "Net-(R5-Pad2)") (class "Default")
      (node (ref "R5") (pin "2") (pinfunction "2_2") (pintype "passive"))
      (node (ref "X1") (pin "8") (pinfunction "8_8") (pintype "passive"))
    )
    (net (code "32") (name "Net-(R8-Pad2)") (class "Default")
      (node (ref "R8") (pin "2") (pinfunction "2_2") (pintype "passive"))
      (node (ref "X1") (pin "7") (pinfunction "7_7") (pintype "passive"))
    )
    (net (code "33") (name "Net-(R9-Pad2)") (class "Default")
      (node (ref "R9") (pin "2") (pinfunction "2_2") (pintype "passive"))
      (node (ref "X2") (pin "8") (pinfunction "8_8") (pintype "passive"))
    )
    (net (code "34") (name "Net-(R10-Pad2)") (class "Default")
      (node (ref "R10") (pin "2") (pinfunction "2_2") (pintype "passive"))
      (node (ref "R11") (pin "1") (pinfunction "1_1") (pintype "passive"))
      (node (ref "R5") (pin "1") (pinfunction "1_1") (pintype "passive"))
    )
    (net (code "35") (name "Net-(R11-Pad2)") (class "Default")
      (node (ref "R11") (pin "2") (pinfunction "2_2") (pintype "passive"))
      (node (ref "X1") (pin "4") (pinfunction "4_4") (pintype "passive"))
    )
    (net (code "36") (name "Net-(R12-Pad1)") (class "Default")
      (node (ref "R12") (pin "1") (pinfunction "1_1") (pintype "passive"))
      (node (ref "R14") (pin "1") (pinfunction "1_1") (pintype "passive"))
      (node (ref "R15") (pin "2") (pinfunction "2_2") (pintype "passive"))
    )
    (net (code "37") (name "Net-(R12-Pad2)") (class "Default")
      (node (ref "R12") (pin "2") (pinfunction "2_2") (pintype "passive"))
      (node (ref "X2") (pin "7") (pinfunction "7_7") (pintype "passive"))
    )
    (net (code "38") (name "Net-(R14-Pad2)") (class "Default")
      (node (ref "R14") (pin "2") (pinfunction "2_2") (pintype "passive"))
      (node (ref "X2") (pin "5") (pinfunction "5_5") (pintype "passive"))
    )
    (net (code "39") (name "Net-(R16-Pad1)") (class "Default")
      (node (ref "R16") (pin "1") (pinfunction "1_1") (pintype "passive"))
      (node (ref "R7") (pin "2") (pinfunction "2_2") (pintype "passive"))
      (node (ref "R9") (pin "1") (pinfunction "1_1") (pintype "passive"))
    )
    (net (code "40") (name "Net-(R16-Pad2)") (class "Default")
      (node (ref "R16") (pin "2") (pinfunction "2_2") (pintype "passive"))
      (node (ref "X2") (pin "4") (pinfunction "4_4") (pintype "passive"))
    )
    (net (code "41") (name "Net-(R17-Pad1)") (class "Default")
      (node (ref "R17") (pin "1") (pinfunction "1_1") (pintype "passive"))
      (node (ref "R18") (pin "2") (pinfunction "2_2") (pintype "passive"))
      (node (ref "R8") (pin "1") (pinfunction "1_1") (pintype "passive"))
    )
    (net (code "42") (name "Net-(R17-Pad2)") (class "Default")
      (node (ref "R17") (pin "2") (pinfunction "2_2") (pintype "passive"))
      (node (ref "X1") (pin "5") (pinfunction "5_5") (pintype "passive"))
    )
    (net (code "43") (name "Net-(T1-RXCT)") (class "Default")
      (node (ref "R6") (pin "2") (pinfunction "2_2") (pintype "passive"))
      (node (ref "T1") (pin "10") (pinfunction "RXCT_10") (pintype "bidirectional"))
      (node (ref "T1") (pin "15") (pinfunction "TXCT_15") (pintype "bidirectional"))
    )
    (net (code "44") (name "Net-(T2-RXCT)") (class "Default")
      (node (ref "R13") (pin "2") (pinfunction "2_2") (pintype "passive"))
      (node (ref "T2") (pin "10") (pinfunction "RXCT_10") (pintype "bidirectional"))
      (node (ref "T2") (pin "15") (pinfunction "TXCT_15") (pintype "bidirectional"))
    )
    (net (code "45") (name "PS0") (class "Default")
      (node (ref "R31") (pin "1") (pinfunction "1_1") (pintype "passive"))
      (node (ref "U3") (pin "114") (pinfunction "PS0_114") (pintype "input"))
    )
    (net (code "46") (name "PS1") (class "Default")
      (node (ref "R30") (pin "1") (pinfunction "1_1") (pintype "passive"))
      (node (ref "U3") (pin "113") (pinfunction "PS1_113") (pintype "input"))
    )
    (net (code "47") (name "PW") (class "Default")
      (node (ref "C18") (pin "1") (pinfunction "1_1") (pintype "passive"))
      (node (ref "C19") (pin "1") (pinfunction "1_1") (pintype "passive"))
      (node (ref "CR1") (pin "1") (pinfunction "C_1") (pintype "passive"))
      (node (ref "J1") (pin "2") (pinfunction "S_2") (pintype "passive"))
      (node (ref "L3") (pin "1") (pinfunction "1_1") (pintype "passive"))
    )
    (net (code "48") (name "PWRDN_N") (class "Default")
      (node (ref "U3") (pin "47") (pinfunction "PWRDN_N_47") (pintype "input"))
    )
    (net (code "49") (name "RST_N") (class "Default")
      (node (ref "C45") (pin "1") (pinfunction "1_1") (pintype "passive"))
      (node (ref "R49") (pin "1") (pinfunction "1_1") (pintype "passive"))
      (node (ref "U$9") (pin "A") (pinfunction "2_A") (pintype "passive"))
      (node (ref "U3") (pin "115") (pinfunction "RST_N_115") (pintype "input"))
    )
    (net (code "50") (name "RX1_ISO_N") (class "Default")
      (node (ref "R21") (pin "2") (pinfunction "2_2") (pintype "passive"))
      (node (ref "T1") (pin "8") (pinfunction "RD-_8") (pintype "bidirectional"))
      (node (ref "U3") (pin "20") (pinfunction "RXM3_20") (pintype "input"))
    )
    (net (code "51") (name "RX1_ISO_P") (class "Default")
      (node (ref "R22") (pin "2") (pinfunction "2_2") (pintype "passive"))
      (node (ref "T1") (pin "6") (pinfunction "RD+_6") (pintype "bidirectional"))
      (node (ref "U3") (pin "19") (pinfunction "RXP3_19") (pintype "input"))
    )
    (net (code "52") (name "RX1_M") (class "Default")
      (node (ref "T1") (pin "9") (pinfunction "RX-_9") (pintype "bidirectional"))
      (node (ref "X1") (pin "2") (pinfunction "2_2") (pintype "passive"))
    )
    (net (code "53") (name "RX1_P") (class "Default")
      (node (ref "T1") (pin "11") (pinfunction "RX+_11") (pintype "bidirectional"))
      (node (ref "X1") (pin "1") (pinfunction "1_1") (pintype "passive"))
    )
    (net (code "54") (name "RX2_ISO_N") (class "Default")
      (node (ref "R25") (pin "2") (pinfunction "2_2") (pintype "passive"))
      (node (ref "T2") (pin "8") (pinfunction "RD-_8") (pintype "bidirectional"))
      (node (ref "U3") (pin "5") (pinfunction "RXM1_5") (pintype "input"))
    )
    (net (code "55") (name "RX2_ISO_P") (class "Default")
      (node (ref "R26") (pin "2") (pinfunction "2_2") (pintype "passive"))
      (node (ref "T2") (pin "6") (pinfunction "RD+_6") (pintype "bidirectional"))
      (node (ref "U3") (pin "4") (pinfunction "RXP1_4") (pintype "input"))
    )
    (net (code "56") (name "RX2_M") (class "Default")
      (node (ref "T2") (pin "9") (pinfunction "RX-_9") (pintype "bidirectional"))
      (node (ref "X2") (pin "2") (pinfunction "2_2") (pintype "passive"))
    )
    (net (code "57") (name "RX2_P") (class "Default")
      (node (ref "T2") (pin "11") (pinfunction "RX+_11") (pintype "bidirectional"))
      (node (ref "X2") (pin "1") (pinfunction "1_1") (pintype "passive"))
    )
    (net (code "58") (name "RX3_ISO_N") (class "Default")
      (node (ref "P1") (pin "R8") (pinfunction "RD-_R8") (pintype "input"))
      (node (ref "R46") (pin "2") (pinfunction "2_2") (pintype "passive"))
      (node (ref "U3") (pin "11") (pinfunction "RXM2_11") (pintype "input"))
    )
    (net (code "59") (name "RX3_ISO_P") (class "Default")
      (node (ref "P1") (pin "R7") (pinfunction "RD+_R7") (pintype "input"))
      (node (ref "R45") (pin "2") (pinfunction "2_2") (pintype "passive"))
      (node (ref "U3") (pin "10") (pinfunction "RXP2_10") (pintype "input"))
    )
    (net (code "60") (name "SCL") (class "Default")
      (node (ref "R37") (pin "1") (pinfunction "1_1") (pintype "passive"))
      (node (ref "R38") (pin "1") (pinfunction "1_1") (pintype "passive"))
      (node (ref "U3") (pin "110") (pinfunction "SPIC/SCL_110") (pintype "bidirectional"))
    )
    (net (code "61") (name "SCL_CPU") (class "Default")
      (node (ref "JP1") (pin "2") (pinfunction "2_2") (pintype "passive"))
      (node (ref "R38") (pin "2") (pinfunction "2_2") (pintype "passive"))
    )
    (net (code "62") (name "SCL_EEPROM") (class "Default")
      (node (ref "R37") (pin "2") (pinfunction "2_2") (pintype "passive"))
      (node (ref "U4") (pin "6") (pinfunction "SCL_6") (pintype "input"))
    )
    (net (code "63") (name "SDA") (class "Default")
      (node (ref "R35") (pin "1") (pinfunction "1_1") (pintype "passive"))
      (node (ref "R36") (pin "1") (pinfunction "1_1") (pintype "passive"))
      (node (ref "U3") (pin "111") (pinfunction "SSPID/SDA_111") (pintype "bidirectional"))
    )
    (net (code "64") (name "SDA_CPU") (class "Default")
      (node (ref "JP1") (pin "3") (pinfunction "3_3") (pintype "passive"))
      (node (ref "R36") (pin "2") (pinfunction "2_2") (pintype "passive"))
    )
    (net (code "65") (name "SDA_EEPROM") (class "Default")
      (node (ref "R35") (pin "2") (pinfunction "2_2") (pintype "passive"))
      (node (ref "U4") (pin "5") (pinfunction "SDA_5") (pintype "bidirectional"))
    )
    (net (code "66") (name "SPIQ") (class "Default")
      (node (ref "R39") (pin "1") (pinfunction "1_1") (pintype "passive"))
      (node (ref "U3") (pin "109") (pinfunction "SPIQ_109") (pintype "output"))
    )
    (net (code "67") (name "SPIQ_CPU") (class "Default")
      (node (ref "JP1") (pin "1") (pinfunction "1_1") (pintype "passive"))
      (node (ref "R39") (pin "2") (pinfunction "2_2") (pintype "passive"))
    )
    (net (code "68") (name "SPIS-N") (class "Default")
      (node (ref "R40") (pin "1") (pinfunction "1_1") (pintype "passive"))
      (node (ref "U3") (pin "112") (pinfunction "SPIS_N_112") (pintype "input"))
    )
    (net (code "69") (name "SPIS-N_CPU") (class "Default")
      (node (ref "JP1") (pin "4") (pinfunction "4_4") (pintype "passive"))
      (node (ref "R40") (pin "2") (pinfunction "2_2") (pintype "passive"))
    )
    (net (code "70") (name "TX1_ISO_N") (class "Default")
      (node (ref "R19") (pin "2") (pinfunction "2_2") (pintype "passive"))
      (node (ref "T1") (pin "3") (pinfunction "TD-_3") (pintype "bidirectional"))
      (node (ref "U3") (pin "23") (pinfunction "TXM3_23") (pintype "output"))
    )
    (net (code "71") (name "TX1_ISO_P") (class "Default")
      (node (ref "R20") (pin "2") (pinfunction "2_2") (pintype "passive"))
      (node (ref "T1") (pin "1") (pinfunction "TD+_1") (pintype "bidirectional"))
      (node (ref "U3") (pin "22") (pinfunction "TXP3_22") (pintype "output"))
    )
    (net (code "72") (name "TX1_M") (class "Default")
      (node (ref "T1") (pin "14") (pinfunction "TX-_14") (pintype "bidirectional"))
      (node (ref "X1") (pin "6") (pinfunction "6_6") (pintype "passive"))
    )
    (net (code "73") (name "TX1_P") (class "Default")
      (node (ref "T1") (pin "16") (pinfunction "TX+_16") (pintype "bidirectional"))
      (node (ref "X1") (pin "3") (pinfunction "3_3") (pintype "passive"))
    )
    (net (code "74") (name "TX2_ISO_N") (class "Default")
      (node (ref "R23") (pin "2") (pinfunction "2_2") (pintype "passive"))
      (node (ref "T2") (pin "3") (pinfunction "TD-_3") (pintype "bidirectional"))
      (node (ref "U3") (pin "8") (pinfunction "TXM1_8") (pintype "output"))
    )
    (net (code "75") (name "TX2_ISO_P") (class "Default")
      (node (ref "R24") (pin "2") (pinfunction "2_2") (pintype "passive"))
      (node (ref "T2") (pin "1") (pinfunction "TD+_1") (pintype "bidirectional"))
      (node (ref "U3") (pin "7") (pinfunction "TXP1_7") (pintype "output"))
    )
    (net (code "76") (name "TX2_M") (class "Default")
      (node (ref "T2") (pin "14") (pinfunction "TX-_14") (pintype "bidirectional"))
      (node (ref "X2") (pin "6") (pinfunction "6_6") (pintype "passive"))
    )
    (net (code "77") (name "TX2_P") (class "Default")
      (node (ref "T2") (pin "16") (pinfunction "TX+_16") (pintype "bidirectional"))
      (node (ref "X2") (pin "3") (pinfunction "3_3") (pintype "passive"))
    )
    (net (code "78") (name "TX3_ISO_N") (class "Default")
      (node (ref "P1") (pin "R2") (pinfunction "TD-_R2") (pintype "input"))
      (node (ref "R33") (pin "2") (pinfunction "2_2") (pintype "passive"))
      (node (ref "U3") (pin "14") (pinfunction "TXM2_14") (pintype "output"))
    )
    (net (code "79") (name "TX3_ISO_P") (class "Default")
      (node (ref "P1") (pin "R1") (pinfunction "TD+_R1") (pintype "input"))
      (node (ref "R32") (pin "2") (pinfunction "2_2") (pintype "passive"))
      (node (ref "U3") (pin "13") (pinfunction "TXP2_13") (pintype "output"))
    )
    (net (code "80") (name "X1") (class "Default")
      (node (ref "C41") (pin "1") (pinfunction "1_1") (pintype "passive"))
      (node (ref "U3") (pin "121") (pinfunction "X1_121") (pintype "input"))
      (node (ref "Y1") (pin "1") (pinfunction "1_1") (pintype "passive"))
    )
    (net (code "81") (name "X2") (class "Default")
      (node (ref "C42") (pin "1") (pinfunction "1_1") (pintype "passive"))
      (node (ref "U3") (pin "122") (pinfunction "X2_122") (pintype "output"))
      (node (ref "Y1") (pin "3") (pinfunction "3_3") (pintype "passive"))
    )
    (net (code "82") (name "unconnected-(U3A-FXSD4-Pad39)") (class "Default")
      (node (ref "U3") (pin "39") (pinfunction "FXSD4_39") (pintype "input"))
    )
    (net (code "83") (name "unconnected-(U3A-FXSD5{slash}FXSD3-Pad38)") (class "Default")
      (node (ref "U3") (pin "38") (pinfunction "FXSD5/FXSD3_38") (pintype "input"))
    )
    (net (code "84") (name "unconnected-(U3A-MDI-XDIS-Pad1)") (class "Default")
      (node (ref "U3") (pin "1") (pinfunction "MDI-XDIS_1") (pintype "input"))
    )
    (net (code "85") (name "unconnected-(U3A-MUX1-Pad45)") (class "Default")
      (node (ref "U3") (pin "45") (pinfunction "MUX1_45") (pintype "passive"))
    )
    (net (code "86") (name "unconnected-(U3A-MUX2-Pad46)") (class "Default")
      (node (ref "U3") (pin "46") (pinfunction "MUX2_46") (pintype "passive"))
    )
    (net (code "87") (name "unconnected-(U3A-PMRXC-Pad60)") (class "Default")
      (node (ref "U3") (pin "60") (pinfunction "PMRXC_60") (pintype "output"))
    )
    (net (code "88") (name "unconnected-(U3A-PMRXD1-Pad64)") (class "Default")
      (node (ref "U3") (pin "64") (pinfunction "PMRXD1_64") (pintype "bidirectional"))
    )
    (net (code "89") (name "unconnected-(U3A-PMRXD2-Pad63)") (class "Default")
      (node (ref "U3") (pin "63") (pinfunction "PMRXD2_63") (pintype "bidirectional"))
    )
    (net (code "90") (name "unconnected-(U3A-PMRXD3-Pad62)") (class "Default")
      (node (ref "U3") (pin "62") (pinfunction "PMRXD3_62") (pintype "bidirectional"))
    )
    (net (code "91") (name "unconnected-(U3A-PMRXDV-Pad61)") (class "Default")
      (node (ref "U3") (pin "61") (pinfunction "PMRXDV_61") (pintype "bidirectional"))
    )
    (net (code "92") (name "unconnected-(U3A-PMTXC-Pad57)") (class "Default")
      (node (ref "U3") (pin "57") (pinfunction "PMTXC_57") (pintype "output"))
    )
    (net (code "93") (name "unconnected-(U3A-PMTXD0-Pad55)") (class "Default")
      (node (ref "U3") (pin "55") (pinfunction "PMTXD0_55") (pintype "input"))
    )
    (net (code "94") (name "unconnected-(U3A-PMTXD1-Pad54)") (class "Default")
      (node (ref "U3") (pin "54") (pinfunction "PMTXD1_54") (pintype "input"))
    )
    (net (code "95") (name "unconnected-(U3A-PMTXD2-Pad53)") (class "Default")
      (node (ref "U3") (pin "53") (pinfunction "PMTXD2_53") (pintype "input"))
    )
    (net (code "96") (name "unconnected-(U3A-PMTXD3-Pad52)") (class "Default")
      (node (ref "U3") (pin "52") (pinfunction "PMTXD3_52") (pintype "input"))
    )
    (net (code "97") (name "unconnected-(U3A-PMTXEN-Pad51)") (class "Default")
      (node (ref "U3") (pin "51") (pinfunction "PMTXEN_51") (pintype "input"))
    )
    (net (code "98") (name "unconnected-(U3A-PMTXER-Pad56)") (class "Default")
      (node (ref "U3") (pin "56") (pinfunction "PMTXER_56") (pintype "input"))
    )
    (net (code "99") (name "unconnected-(U3A-RESERVE-Pad48)") (class "Default")
      (node (ref "U3") (pin "48") (pinfunction "RESERVE_48") (pintype "passive"))
    )
    (net (code "100") (name "unconnected-(U3B-LED1-2-Pad104)") (class "Default")
      (node (ref "U3") (pin "104") (pinfunction "LED1-2_104") (pintype "bidirectional"))
    )
    (net (code "101") (name "unconnected-(U3B-LED2-2-Pad101)") (class "Default")
      (node (ref "U3") (pin "101") (pinfunction "LED2-2_101") (pintype "bidirectional"))
    )
    (net (code "102") (name "unconnected-(U3B-LED3-2-Pad96)") (class "Default")
      (node (ref "U3") (pin "96") (pinfunction "LED3-2_96") (pintype "bidirectional"))
    )
    (net (code "103") (name "unconnected-(U3B-LED4-0-Pad95)") (class "Default")
      (node (ref "U3") (pin "95") (pinfunction "LED4-0_95") (pintype "bidirectional"))
    )
    (net (code "104") (name "unconnected-(U3B-LED4-1-Pad94)") (class "Default")
      (node (ref "U3") (pin "94") (pinfunction "LED4-1_94") (pintype "bidirectional"))
    )
    (net (code "105") (name "unconnected-(U3B-LED4-2-Pad93)") (class "Default")
      (node (ref "U3") (pin "93") (pinfunction "LED4-2_93") (pintype "bidirectional"))
    )
    (net (code "106") (name "unconnected-(U3B-LED5-0-Pad92)") (class "Default")
      (node (ref "U3") (pin "92") (pinfunction "LED5-0_92") (pintype "bidirectional"))
    )
    (net (code "107") (name "unconnected-(U3B-LED5-1-Pad91)") (class "Default")
      (node (ref "U3") (pin "91") (pinfunction "LED5-1_91") (pintype "bidirectional"))
    )
    (net (code "108") (name "unconnected-(U3B-LED5-2-Pad90)") (class "Default")
      (node (ref "U3") (pin "90") (pinfunction "LED5-2_90") (pintype "bidirectional"))
    )
    (net (code "109") (name "unconnected-(U3B-MDC-Pad107)") (class "Default")
      (node (ref "U3") (pin "107") (pinfunction "MDC_107") (pintype "input"))
    )
    (net (code "110") (name "unconnected-(U3B-MDIO-Pad108)") (class "Default")
      (node (ref "U3") (pin "108") (pinfunction "MDIO_108") (pintype "bidirectional"))
    )
    (net (code "111") (name "unconnected-(U3B-NC-Pad120)") (class "Default")
      (node (ref "U3") (pin "120") (pinfunction "NC_120") (pintype "no_connect"))
    )
    (net (code "112") (name "unconnected-(U3B-PCOL-Pad68)") (class "Default")
      (node (ref "U3") (pin "68") (pinfunction "PCOL_68") (pintype "bidirectional"))
    )
    (net (code "113") (name "unconnected-(U3B-PCRS-Pad67)") (class "Default")
      (node (ref "U3") (pin "67") (pinfunction "PCRS_67") (pintype "bidirectional"))
    )
    (net (code "114") (name "unconnected-(U3B-PMRXD0-Pad65)") (class "Default")
      (node (ref "U3") (pin "65") (pinfunction "PMRXD0_65") (pintype "bidirectional"))
    )
    (net (code "115") (name "unconnected-(U3B-PMRXER-Pad66)") (class "Default")
      (node (ref "U3") (pin "66") (pinfunction "PMRXER_66") (pintype "bidirectional"))
    )
    (net (code "116") (name "unconnected-(U3B-SCANEN-Pad119)") (class "Default")
      (node (ref "U3") (pin "119") (pinfunction "SCANEN_119") (pintype "input"))
    )
    (net (code "117") (name "unconnected-(U3B-SCOL-Pad84)") (class "Default")
      (node (ref "U3") (pin "84") (pinfunction "SCOL_84") (pintype "bidirectional"))
    )
    (net (code "118") (name "unconnected-(U3B-SCONF0-Pad87)") (class "Default")
      (node (ref "U3") (pin "87") (pinfunction "SCONF0_87") (pintype "input"))
    )
    (net (code "119") (name "unconnected-(U3B-SCONF1-Pad86)") (class "Default")
      (node (ref "U3") (pin "86") (pinfunction "SCONF1_86") (pintype "input"))
    )
    (net (code "120") (name "unconnected-(U3B-SCRS-Pad85)") (class "Default")
      (node (ref "U3") (pin "85") (pinfunction "SCRS_85") (pintype "bidirectional"))
    )
    (net (code "121") (name "unconnected-(U3B-SMRXC-Pad78)") (class "Default")
      (node (ref "U3") (pin "78") (pinfunction "SMRXC_78") (pintype "bidirectional"))
    )
    (net (code "122") (name "unconnected-(U3B-SMRXD0-Pad83)") (class "Default")
      (node (ref "U3") (pin "83") (pinfunction "SMRXD0_83") (pintype "bidirectional"))
    )
    (net (code "123") (name "unconnected-(U3B-SMRXD1-Pad82)") (class "Default")
      (node (ref "U3") (pin "82") (pinfunction "SMRXD1_82") (pintype "bidirectional"))
    )
    (net (code "124") (name "unconnected-(U3B-SMRXD2-Pad81)") (class "Default")
      (node (ref "U3") (pin "81") (pinfunction "SMRXD2_81") (pintype "bidirectional"))
    )
    (net (code "125") (name "unconnected-(U3B-SMRXD3-Pad80)") (class "Default")
      (node (ref "U3") (pin "80") (pinfunction "SMRXD3_80") (pintype "bidirectional"))
    )
    (net (code "126") (name "unconnected-(U3B-SMRXDV-Pad79)") (class "Default")
      (node (ref "U3") (pin "79") (pinfunction "SMRXDV_79") (pintype "bidirectional"))
    )
    (net (code "127") (name "unconnected-(U3B-SMTXC-Pad75)") (class "Default")
      (node (ref "U3") (pin "75") (pinfunction "SMTXC_75") (pintype "bidirectional"))
    )
    (net (code "128") (name "unconnected-(U3B-SMTXD0-Pad73)") (class "Default")
      (node (ref "U3") (pin "73") (pinfunction "SMTXD0_73") (pintype "input"))
    )
    (net (code "129") (name "unconnected-(U3B-SMTXD1-Pad72)") (class "Default")
      (node (ref "U3") (pin "72") (pinfunction "SMTXD1_72") (pintype "input"))
    )
    (net (code "130") (name "unconnected-(U3B-SMTXD2-Pad71)") (class "Default")
      (node (ref "U3") (pin "71") (pinfunction "SMTXD2_71") (pintype "input"))
    )
    (net (code "131") (name "unconnected-(U3B-SMTXD3-Pad70)") (class "Default")
      (node (ref "U3") (pin "70") (pinfunction "SMTXD3_70") (pintype "input"))
    )
    (net (code "132") (name "unconnected-(U3B-SMTXEN-Pad69)") (class "Default")
      (node (ref "U3") (pin "69") (pinfunction "SMTXEN_69") (pintype "input"))
    )
    (net (code "133") (name "unconnected-(U3B-SMTXER-Pad74)") (class "Default")
      (node (ref "U3") (pin "74") (pinfunction "SMTXER_74") (pintype "input"))
    )
    (net (code "134") (name "unconnected-(U3B-TEST2-Pad128)") (class "Default")
      (node (ref "U3") (pin "128") (pinfunction "TEST2_128") (pintype "passive"))
    )
    (net (code "135") (name "unconnected-(U3B-TESTEN-Pad118)") (class "Default")
      (node (ref "U3") (pin "118") (pinfunction "TESTEN_118") (pintype "input"))
    )
  )
)
